# max3232.net
KiCad netlist of a schematic drawn in EAGLE
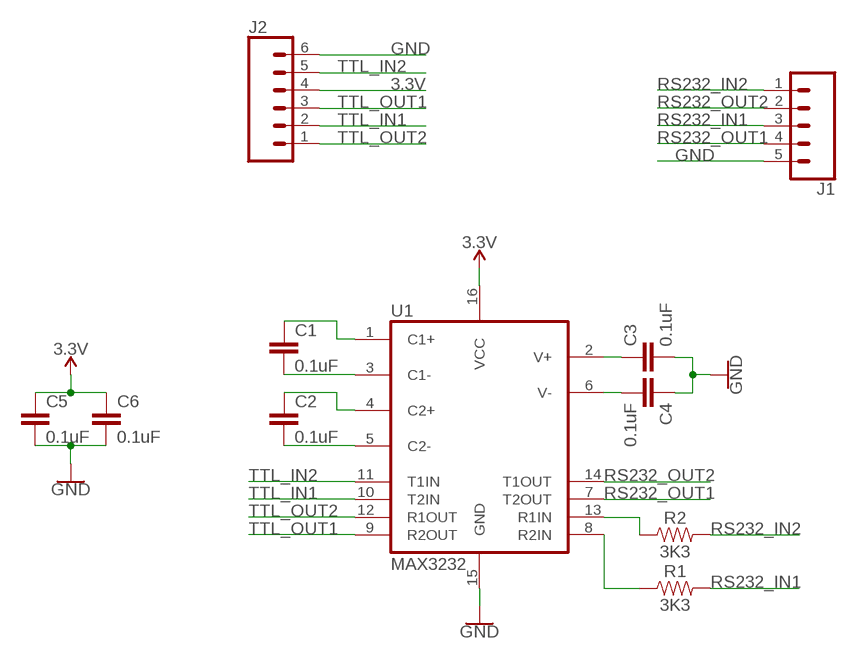
[diagram p0: schematic, sheet 1]

(export (version "E")
  (design (tool "Eeschema 10.0.6"))
  (components
    (comp (ref "C1")
      (value "0.1uF")
      (footprint "eagle-import:0805")
      (libsource (lib "eagle-import") (part "1.0UF-0805-25V-(+80/-20%)"))
    )
    (comp (ref "C2")
      (value "0.1uF")
      (footprint "eagle-import:0805")
      (libsource (lib "eagle-import") (part "1.0UF-0805-25V-(+80/-20%)"))
    )
    (comp (ref "C3")
      (value "0.1uF")
      (footprint "eagle-import:0805")
      (libsource (lib "eagle-import") (part "1.0UF-0805-25V-(+80/-20%)"))
    )
    (comp (ref "C4")
      (value "0.1uF")
      (footprint "eagle-import:0805")
      (libsource (lib "eagle-import") (part "1.0UF-0805-25V-(+80/-20%)"))
    )
    (comp (ref "C5")
      (value "0.1uF")
      (footprint "eagle-import:0805")
      (libsource (lib "eagle-import") (part "1.0UF-0805-25V-(+80/-20%)"))
    )
    (comp (ref "C6")
      (value "0.1uF")
      (footprint "eagle-import:0805")
      (libsource (lib "eagle-import") (part "1.0UF-0805-25V-(+80/-20%)"))
    )
    (comp (ref "J1")
      (value "CONN_05")
      (footprint "eagle-import:1X05")
      (libsource (lib "eagle-import") (part "CONN_05"))
    )
    (comp (ref "J2")
      (value "CONN_06SILK_FEMALE_PTH")
      (footprint "eagle-import:1X06")
      (libsource (lib "eagle-import") (part "CONN_06SILK_FEMALE_PTH"))
    )
    (comp (ref "R1")
      (value "3K3")
      (footprint "eagle-import:1206")
      (libsource (lib "eagle-import") (part "RESISTOR1206"))
    )
    (comp (ref "R2")
      (value "3K3")
      (footprint "eagle-import:1206")
      (libsource (lib "eagle-import") (part "RESISTOR1206"))
    )
    (comp (ref "U1")
      (value "MAX3232")
      (footprint "eagle-import:SO16")
      (libsource (lib "eagle-import") (part "MAX2323SOIC16"))
    )
  )
  (nets
    (net (code "1") (name "/RS232_IN1") (class "Default")
      (node (ref "J1") (pin "3") (pinfunction "3_3") (pintype "passive"))
      (node (ref "R1") (pin "2") (pinfunction "2_2") (pintype "passive"))
    )
    (net (code "2") (name "/RS232_IN2") (class "Default")
      (node (ref "J1") (pin "1") (pinfunction "1_1") (pintype "passive"))
      (node (ref "R2") (pin "2") (pinfunction "2_2") (pintype "passive"))
    )
    (net (code "3") (name "/RS232_OUT1") (class "Default")
      (node (ref "J1") (pin "4") (pinfunction "4_4") (pintype "passive"))
      (node (ref "U1") (pin "7") (pinfunction "T2OUT_7") (pintype "output"))
    )
    (net (code "4") (name "/RS232_OUT2") (class "Default")
      (node (ref "J1") (pin "2") (pinfunction "2_2") (pintype "passive"))
      (node (ref "U1") (pin "14") (pinfunction "T1OUT_14") (pintype "output"))
    )
    (net (code "5") (name "/TTL_IN1") (class "Default")
      (node (ref "J2") (pin "2") (pinfunction "2_2") (pintype "passive"))
      (node (ref "U1") (pin "10") (pinfunction "T2IN_10") (pintype "input"))
    )
    (net (code "6") (name "/TTL_IN2") (class "Default")
      (node (ref "J2") (pin "5") (pinfunction "5_5") (pintype "passive"))
      (node (ref "U1") (pin "11") (pinfunction "T1IN_11") (pintype "input"))
    )
    (net (code "7") (name "/TTL_OUT1") (class "Default")
      (node (ref "J2") (pin "3") (pinfunction "3_3") (pintype "passive"))
      (node (ref "U1") (pin "9") (pinfunction "R2OUT_9") (pintype "output"))
    )
    (net (code "8") (name "/TTL_OUT2") (class "Default")
      (node (ref "J2") (pin "1") (pinfunction "1_1") (pintype "passive"))
      (node (ref "U1") (pin "12") (pinfunction "R1OUT_12") (pintype "output"))
    )
    (net (code "9") (name "3.3V") (class "Default")
      (node (ref "C5") (pin "1") (pinfunction "1_1") (pintype "passive"))
      (node (ref "C6") (pin "1") (pinfunction "1_1") (pintype "passive"))
      (node (ref "J2") (pin "4") (pinfunction "4_4") (pintype "passive"))
      (node (ref "U1") (pin "16") (pinfunction "VCC_16") (pintype "bidirectional"))
    )
    (net (code "10") (name "GND") (class "Default")
      (node (ref "C3") (pin "2") (pinfunction "2_2") (pintype "passive"))
      (node (ref "C4") (pin "1") (pinfunction "1_1") (pintype "passive"))
      (node (ref "C5") (pin "2") (pinfunction "2_2") (pintype "passive"))
      (node (ref "C6") (pin "2") (pinfunction "2_2") (pintype "passive"))
      (node (ref "J1") (pin "5") (pinfunction "5_5") (pintype "passive"))
      (node (ref "J2") (pin "6") (pinfunction "6_6") (pintype "passive"))
      (node (ref "U1") (pin "15") (pinfunction "GND_15") (pintype "bidirectional"))
    )
    (net (code "11") (name "Net-(U1-C1+)") (class "Default")
      (node (ref "C1") (pin "1") (pinfunction "1_1") (pintype "passive"))
      (node (ref "U1") (pin "1") (pinfunction "C1+_1") (pintype "bidirectional"))
    )
    (net (code "12") (name "Net-(U1-C1-)") (class "Default")
      (node (ref "C1") (pin "2") (pinfunction "2_2") (pintype "passive"))
      (node (ref "U1") (pin "3") (pinfunction "C1-_3") (pintype "bidirectional"))
    )
    (net (code "13") (name "Net-(U1-C2+)") (class "Default")
      (node (ref "C2") (pin "1") (pinfunction "1_1") (pintype "passive"))
      (node (ref "U1") (pin "4") (pinfunction "C2+_4") (pintype "bidirectional"))
    )
    (net (code "14") (name "Net-(U1-C2-)") (class "Default")
      (node (ref "C2") (pin "2") (pinfunction "2_2") (pintype "passive"))
      (node (ref "U1") (pin "5") (pinfunction "C2-_5") (pintype "bidirectional"))
    )
    (net (code "15") (name "Net-(U1-R1IN)") (class "Default")
      (node (ref "R2") (pin "1") (pinfunction "1_1") (pintype "passive"))
      (node (ref "U1") (pin "13") (pinfunction "R1IN_13") (pintype "input"))
    )
    (net (code "16") (name "Net-(U1-R2IN)") (class "Default")
      (node (ref "R1") (pin "1") (pinfunction "1_1") (pintype "passive"))
      (node (ref "U1") (pin "8") (pinfunction "R2IN_8") (pintype "input"))
    )
    (net (code "17") (name "Net-(U1-V+)") (class "Default")
      (node (ref "C3") (pin "1") (pinfunction "1_1") (pintype "passive"))
      (node (ref "U1") (pin "2") (pinfunction "V+_2") (pintype "bidirectional"))
    )
    (net (code "18") (name "Net-(U1-V-)") (class "Default")
      (node (ref "C4") (pin "2") (pinfunction "2_2") (pintype "passive"))
      (node (ref "U1") (pin "6") (pinfunction "V-_6") (pintype "bidirectional"))
    )
  )
)
